# bugs.net
KiCad netlist of a schematic drawn in EAGLE
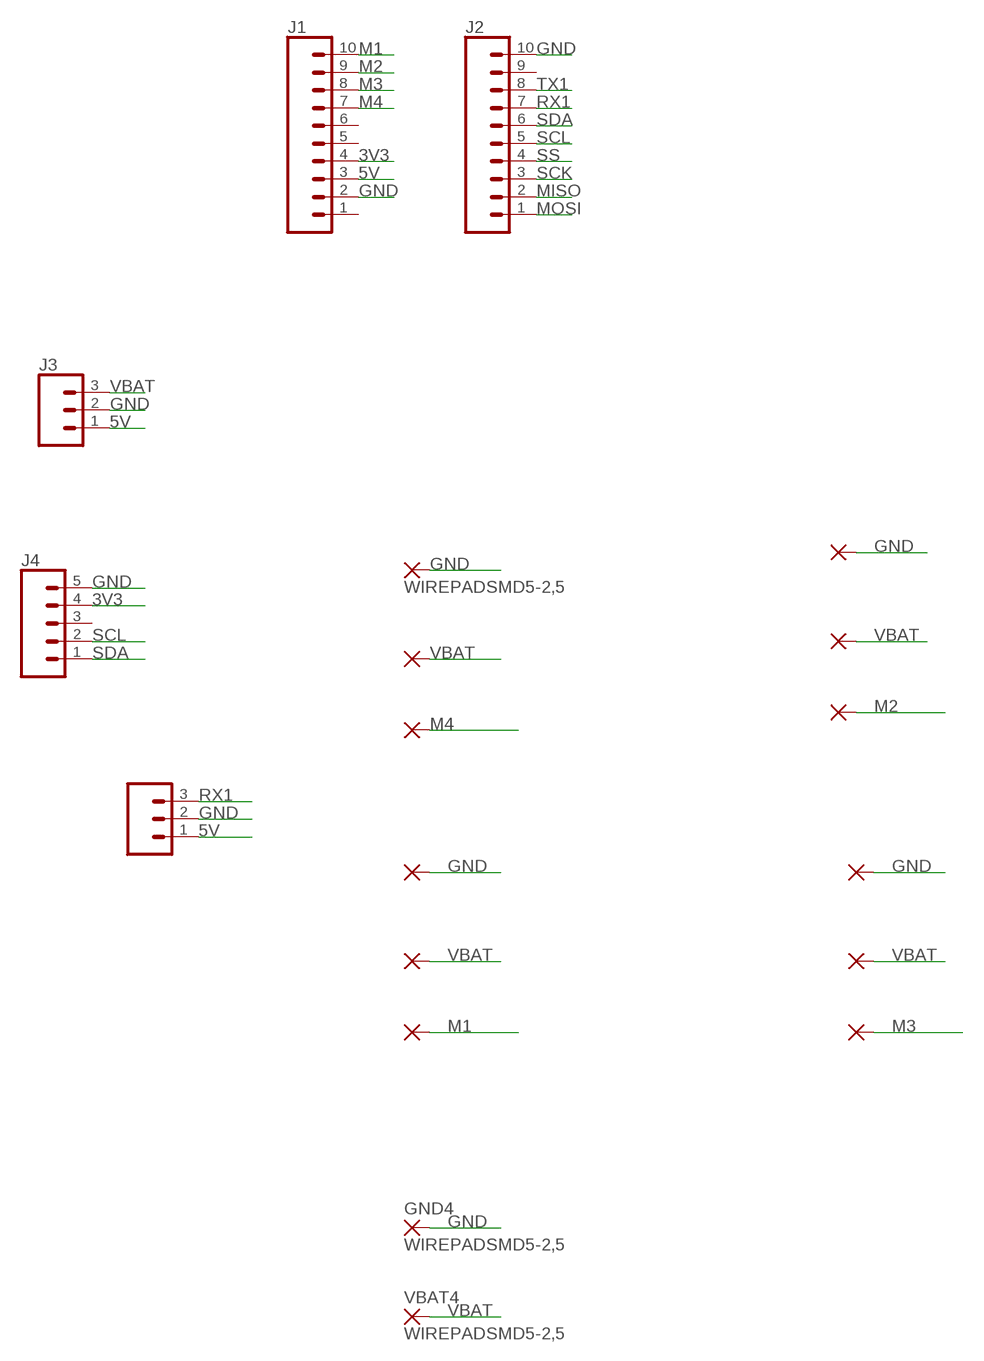
[diagram p0: schematic, sheet 1]

(export (version "E")
  (design (tool "Eeschema 10.0.6"))
  (components
    (comp (ref "GND")
      (value "WIREPADSMD5-2,5")
      (footprint "eagle-import:5-2,5")
      (libsource (lib "eagle-import") (part "WIREPADSMD5-2,5"))
    )
    (comp (ref "GND1")
      (value "WIREPADSMD5-2,5")
      (footprint "eagle-import:5-2,5")
      (libsource (lib "eagle-import") (part "WIREPADSMD5-2,5"))
    )
    (comp (ref "GND2")
      (value "WIREPADSMD5-2,5")
      (footprint "eagle-import:5-2,5")
      (libsource (lib "eagle-import") (part "WIREPADSMD5-2,5"))
    )
    (comp (ref "GND3")
      (value "WIREPADSMD5-2,5")
      (footprint "eagle-import:5-2,5")
      (libsource (lib "eagle-import") (part "WIREPADSMD5-2,5"))
    )
    (comp (ref "GND4")
      (value "WIREPADSMD5-2,5")
      (footprint "eagle-import:5-2,5")
      (libsource (lib "eagle-import") (part "WIREPADSMD5-2,5"))
    )
    (comp (ref "J1")
      (value "CONN_10NO_SILK_PTH_FEMALE")
      (footprint "eagle-import:1X10_NO_SILK")
      (libsource (lib "eagle-import") (part "CONN_10NO_SILK_PTH_FEMALE"))
    )
    (comp (ref "J2")
      (value "CONN_10NO_SILK_PTH_FEMALE")
      (footprint "eagle-import:1X10_NO_SILK")
      (libsource (lib "eagle-import") (part "CONN_10NO_SILK_PTH_FEMALE"))
    )
    (comp (ref "J3")
      (value "CONN_031X03_NO_SILK")
      (footprint "eagle-import:1X03_NO_SILK")
      (libsource (lib "eagle-import") (part "CONN_031X03_NO_SILK"))
    )
    (comp (ref "J4")
      (value "CONN_05NO_SILK")
      (footprint "eagle-import:1X05_NO_SILK")
      (libsource (lib "eagle-import") (part "CONN_05NO_SILK"))
    )
    (comp (ref "J5")
      (value "CONN_031X03_NO_SILK")
      (footprint "eagle-import:1X03_NO_SILK")
      (libsource (lib "eagle-import") (part "CONN_031X03_NO_SILK"))
    )
    (comp (ref "M1")
      (value "WIREPADSMD5-2,5")
      (footprint "eagle-import:5-2,5")
      (libsource (lib "eagle-import") (part "WIREPADSMD5-2,5"))
    )
    (comp (ref "M2")
      (value "WIREPADSMD5-2,5")
      (footprint "eagle-import:5-2,5")
      (libsource (lib "eagle-import") (part "WIREPADSMD5-2,5"))
    )
    (comp (ref "M3")
      (value "WIREPADSMD5-2,5")
      (footprint "eagle-import:5-2,5")
      (libsource (lib "eagle-import") (part "WIREPADSMD5-2,5"))
    )
    (comp (ref "M4")
      (value "WIREPADSMD5-2,5")
      (footprint "eagle-import:5-2,5")
      (libsource (lib "eagle-import") (part "WIREPADSMD5-2,5"))
    )
    (comp (ref "VBAT")
      (value "WIREPADSMD5-2,5")
      (footprint "eagle-import:5-2,5")
      (libsource (lib "eagle-import") (part "WIREPADSMD5-2,5"))
    )
    (comp (ref "VBAT1")
      (value "WIREPADSMD5-2,5")
      (footprint "eagle-import:5-2,5")
      (libsource (lib "eagle-import") (part "WIREPADSMD5-2,5"))
    )
    (comp (ref "VBAT2")
      (value "WIREPADSMD5-2,5")
      (footprint "eagle-import:5-2,5")
      (libsource (lib "eagle-import") (part "WIREPADSMD5-2,5"))
    )
    (comp (ref "VBAT3")
      (value "WIREPADSMD5-2,5")
      (footprint "eagle-import:5-2,5")
      (libsource (lib "eagle-import") (part "WIREPADSMD5-2,5"))
    )
    (comp (ref "VBAT4")
      (value "WIREPADSMD5-2,5")
      (footprint "eagle-import:5-2,5")
      (libsource (lib "eagle-import") (part "WIREPADSMD5-2,5"))
    )
  )
  (nets
    (net (code "1") (name "/3V3") (class "Default")
      (node (ref "J1") (pin "4") (pinfunction "4_4") (pintype "passive"))
      (node (ref "J4") (pin "4") (pinfunction "4_4") (pintype "passive"))
    )
    (net (code "2") (name "/5V") (class "Default")
      (node (ref "J1") (pin "3") (pinfunction "3_3") (pintype "passive"))
      (node (ref "J3") (pin "1") (pinfunction "1_1") (pintype "passive"))
      (node (ref "J5") (pin "1") (pinfunction "1_1") (pintype "passive"))
    )
    (net (code "3") (name "/GND") (class "Default")
      (node (ref "GND") (pin "1") (pinfunction "P_1") (pintype "passive"))
      (node (ref "GND1") (pin "1") (pinfunction "P_1") (pintype "passive"))
      (node (ref "GND2") (pin "1") (pinfunction "P_1") (pintype "passive"))
      (node (ref "GND3") (pin "1") (pinfunction "P_1") (pintype "passive"))
      (node (ref "GND4") (pin "1") (pinfunction "P_1") (pintype "passive"))
      (node (ref "J1") (pin "2") (pinfunction "2_2") (pintype "passive"))
      (node (ref "J2") (pin "10") (pinfunction "10_10") (pintype "passive"))
      (node (ref "J3") (pin "2") (pinfunction "2_2") (pintype "passive"))
      (node (ref "J4") (pin "5") (pinfunction "5_5") (pintype "passive"))
      (node (ref "J5") (pin "2") (pinfunction "2_2") (pintype "passive"))
    )
    (net (code "4") (name "/M1") (class "Default")
      (node (ref "J1") (pin "10") (pinfunction "10_10") (pintype "passive"))
      (node (ref "M1") (pin "1") (pinfunction "P_1") (pintype "passive"))
    )
    (net (code "5") (name "/M2") (class "Default")
      (node (ref "J1") (pin "9") (pinfunction "9_9") (pintype "passive"))
      (node (ref "M2") (pin "1") (pinfunction "P_1") (pintype "passive"))
    )
    (net (code "6") (name "/M3") (class "Default")
      (node (ref "J1") (pin "8") (pinfunction "8_8") (pintype "passive"))
      (node (ref "M3") (pin "1") (pinfunction "P_1") (pintype "passive"))
    )
    (net (code "7") (name "/M4") (class "Default")
      (node (ref "J1") (pin "7") (pinfunction "7_7") (pintype "passive"))
      (node (ref "M4") (pin "1") (pinfunction "P_1") (pintype "passive"))
    )
    (net (code "8") (name "/MISO") (class "Default")
      (node (ref "J2") (pin "2") (pinfunction "2_2") (pintype "passive"))
    )
    (net (code "9") (name "/MOSI") (class "Default")
      (node (ref "J2") (pin "1") (pinfunction "1_1") (pintype "passive"))
    )
    (net (code "10") (name "/RX1") (class "Default")
      (node (ref "J2") (pin "7") (pinfunction "7_7") (pintype "passive"))
      (node (ref "J5") (pin "3") (pinfunction "3_3") (pintype "passive"))
    )
    (net (code "11") (name "/SCK") (class "Default")
      (node (ref "J2") (pin "3") (pinfunction "3_3") (pintype "passive"))
    )
    (net (code "12") (name "/SCL") (class "Default")
      (node (ref "J2") (pin "5") (pinfunction "5_5") (pintype "passive"))
      (node (ref "J4") (pin "2") (pinfunction "2_2") (pintype "passive"))
    )
    (net (code "13") (name "/SDA") (class "Default")
      (node (ref "J2") (pin "6") (pinfunction "6_6") (pintype "passive"))
      (node (ref "J4") (pin "1") (pinfunction "1_1") (pintype "passive"))
    )
    (net (code "14") (name "/SS") (class "Default")
      (node (ref "J2") (pin "4") (pinfunction "4_4") (pintype "passive"))
    )
    (net (code "15") (name "/TX1") (class "Default")
      (node (ref "J2") (pin "8") (pinfunction "8_8") (pintype "passive"))
    )
    (net (code "16") (name "/VBAT") (class "Default")
      (node (ref "J3") (pin "3") (pinfunction "3_3") (pintype "passive"))
      (node (ref "VBAT") (pin "1") (pinfunction "P_1") (pintype "passive"))
      (node (ref "VBAT1") (pin "1") (pinfunction "P_1") (pintype "passive"))
      (node (ref "VBAT2") (pin "1") (pinfunction "P_1") (pintype "passive"))
      (node (ref "VBAT3") (pin "1") (pinfunction "P_1") (pintype "passive"))
      (node (ref "VBAT4") (pin "1") (pinfunction "P_1") (pintype "passive"))
    )
    (net (code "17") (name "unconnected-(J1-Pad1)") (class "Default")
      (node (ref "J1") (pin "1") (pinfunction "1_1") (pintype "passive"))
    )
    (net (code "18") (name "unconnected-(J1-Pad5)") (class "Default")
      (node (ref "J1") (pin "5") (pinfunction "5_5") (pintype "passive"))
    )
    (net (code "19") (name "unconnected-(J1-Pad6)") (class "Default")
      (node (ref "J1") (pin "6") (pinfunction "6_6") (pintype "passive"))
    )
    (net (code "20") (name "unconnected-(J2-Pad9)") (class "Default")
      (node (ref "J2") (pin "9") (pinfunction "9_9") (pintype "passive"))
    )
    (net (code "21") (name "unconnected-(J4-Pad3)") (class "Default")
      (node (ref "J4") (pin "3") (pinfunction "3_3") (pintype "passive"))
    )
  )
)
